# PWM_OUTPUT.net
KiCad netlist of a schematic drawn in Altium Designer
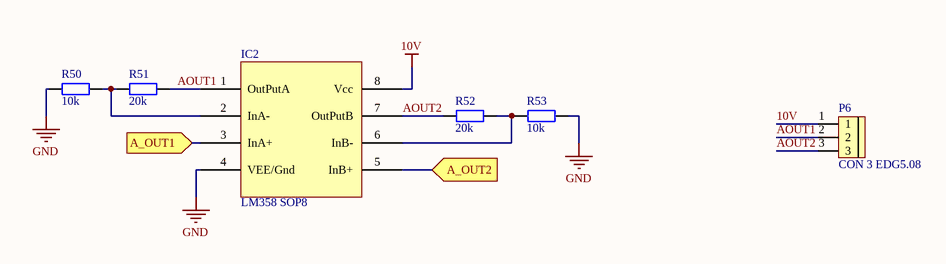
[diagram p0: PWM_OUTPUT.SchDoc]

(export (version "E")
  (design (tool "Eeschema 10.0.6"))
  (components
    (comp (ref "IC2")
      (value "LM358 SOP8")
      (footprint "SOP 8")
      (description "Dán")
      (libsource (lib "Altium_Lib_by_KhueNguyenCreator") (part "LM358 SOP8"))
    )
    (comp (ref "P6")
      (value "CON 3 EDG5.08")
      (footprint "CON 3 3EDG5.08")
      (description "Cắm")
      (libsource (lib "Altium_Lib_by_KhueNguyenCreator") (part "CON 3 EDG5.08"))
    )
    (comp (ref "R50")
      (value "10k")
      (footprint "tro smd 0805")
      (description "Dán")
      (libsource (lib "Altium_Lib_by_KhueNguyenCreator") (part "Tro 0805 1% 10k"))
    )
    (comp (ref "R51")
      (value "20k")
      (footprint "tro smd 0805")
      (description "Dán")
      (libsource (lib "Altium_Lib_by_KhueNguyenCreator") (part "Tro 0805 5% 20k"))
    )
    (comp (ref "R52")
      (value "20k")
      (footprint "tro smd 0805")
      (description "Dán")
      (libsource (lib "Altium_Lib_by_KhueNguyenCreator") (part "Tro 0805 5% 20k"))
    )
    (comp (ref "R53")
      (value "10k")
      (footprint "tro smd 0805")
      (description "Dán")
      (libsource (lib "Altium_Lib_by_KhueNguyenCreator") (part "Tro 0805 1% 10k"))
    )
  )
  (nets
    (net (code "1") (name "/AOUT1") (class "Default")
      (node (ref "IC2") (pin "1") (pinfunction "OutPutA_1") (pintype "passive"))
      (node (ref "P6") (pin "2") (pinfunction "2_2") (pintype "passive"))
      (node (ref "R51") (pin "2") (pinfunction "2_2") (pintype "passive"))
    )
    (net (code "2") (name "/AOUT2") (class "Default")
      (node (ref "IC2") (pin "7") (pinfunction "OutPutB_7") (pintype "passive"))
      (node (ref "P6") (pin "3") (pinfunction "3_3") (pintype "passive"))
      (node (ref "R52") (pin "1") (pinfunction "1_1") (pintype "passive"))
    )
    (net (code "3") (name "/A_OUT1") (class "Default")
      (node (ref "IC2") (pin "3") (pinfunction "InA+_3") (pintype "passive"))
    )
    (net (code "4") (name "/A_OUT2") (class "Default")
      (node (ref "IC2") (pin "5") (pinfunction "InB+_5") (pintype "passive"))
    )
    (net (code "5") (name "10V") (class "Default")
      (node (ref "IC2") (pin "8") (pinfunction "Vcc_8") (pintype "passive"))
      (node (ref "P6") (pin "1") (pinfunction "1_1") (pintype "passive"))
    )
    (net (code "6") (name "GND") (class "Default")
      (node (ref "IC2") (pin "4") (pinfunction "VEE/Gnd_4") (pintype "passive"))
      (node (ref "R50") (pin "1") (pinfunction "1_1") (pintype "passive"))
      (node (ref "R53") (pin "2") (pinfunction "2_2") (pintype "passive"))
    )
    (net (code "7") (name "Net-(IC2-InA-)") (class "Default")
      (node (ref "IC2") (pin "2") (pinfunction "InA-_2") (pintype "passive"))
      (node (ref "R50") (pin "2") (pinfunction "2_2") (pintype "passive"))
      (node (ref "R51") (pin "1") (pinfunction "1_1") (pintype "passive"))
    )
    (net (code "8") (name "Net-(IC2-InB-)") (class "Default")
      (node (ref "IC2") (pin "6") (pinfunction "InB-_6") (pintype "passive"))
      (node (ref "R52") (pin "2") (pinfunction "2_2") (pintype "passive"))
      (node (ref "R53") (pin "1") (pinfunction "1_1") (pintype "passive"))
    )
  )
)
